# USB-COM.net
KiCad netlist of a schematic drawn in Altium Designer
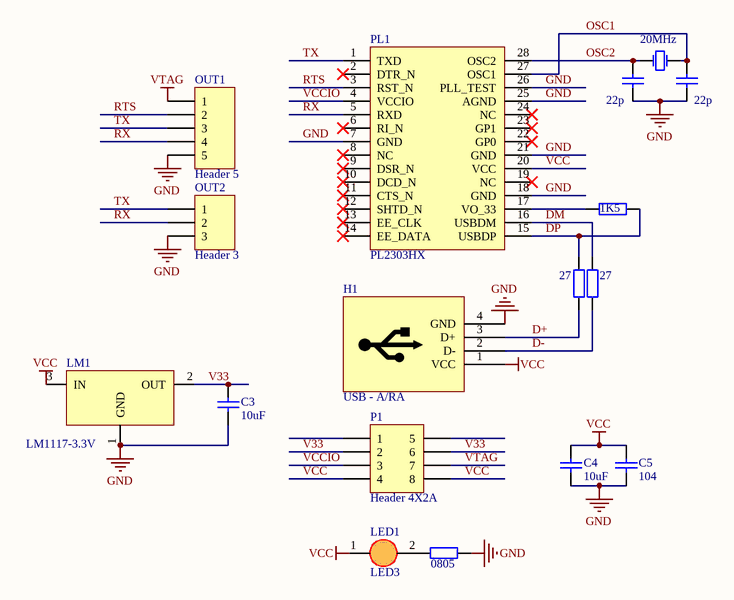
[diagram p0: USB-COM.SchDoc]

(export (version "E")
  (design (tool "Eeschema 10.0.6"))
  (components
    (comp (ref "C1")
      (value "22p")
      (footprint "C0805")
      (description "Capacitor")
      (fields (field (name "Comment") "Capacitor Ceramic") (field (name "PUBLISHER") "Altium Limited"))
      (libsource (lib "Schematic") (part "CapSMD"))
    )
    (comp (ref "C2")
      (value "22p")
      (footprint "C0805")
      (description "Capacitor")
      (fields (field (name "Comment") "Capacitor Ceramic") (field (name "PUBLISHER") "Altium Limited"))
      (libsource (lib "Schematic") (part "CapSMD"))
    )
    (comp (ref "C3") (value "10uF") (footprint "C1206") (libsource (lib "Schematic") (part "Cap SMD 1206")))
    (comp (ref "C4") (value "10uF") (footprint "C1206") (libsource (lib "Schematic") (part "Cap SMD 1206")))
    (comp (ref "C5")
      (value "104")
      (footprint "C0805")
      (description "Capacitor")
      (fields (field (name "Comment") "Capacitor Ceramic") (field (name "PUBLISHER") "Altium Limited"))
      (libsource (lib "Schematic") (part "CapSMD"))
    )
    (comp (ref "H1")
      (value "USB - A/RA")
      (footprint "USB-A-RA")
      (libsource (lib "Schematic") (part "USB - A/RA"))
    )
    (comp (ref "LED1")
      (value "LED3")
      (footprint "LED0805")
      (description "LED 3mm")
      (libsource (lib "Schematic") (part "LED 3mm"))
    )
    (comp (ref "LM1")
      (value "LM1117-3.3V")
      (footprint "LM1117-SOP")
      (description "800mA Low-Dropout Linear Regulator")
      (fields (field (name "CREATOR") "Nguyen Ba Bien"))
      (libsource (lib "General IC") (part "LM1117"))
    )
    (comp (ref "OUT1")
      (value "Header 5")
      (footprint "HDR1X5")
      (description "Header, 5-Pin")
      (fields (field (name "PUBLISHER") "Altium Limited"))
      (libsource (lib "Schematic") (part "Header 5"))
    )
    (comp (ref "OUT2")
      (value "Header 3")
      (footprint "HDR1X3")
      (description "Header, 3-Pin")
      (fields (field (name "PUBLISHER") "Altium Limited"))
      (libsource (lib "Schematic") (part "Header 3"))
    )
    (comp (ref "P1")
      (value "Header 4X2A")
      (footprint "HDR2X4_CEN")
      (description "Header, 4-Pin, Dual row")
      (fields (field (name "PUBLISHER") "Altium Limited"))
      (libsource (lib "Schematic") (part "Header 4X2A"))
    )
    (comp (ref "PL1")
      (value "PL2303HX")
      (footprint "PL2303-HX")
      (description "PL-2303 USB to RS-232 Bridge Controller")
      (fields (field (name "CREATOR") "Nguyen Ba Bien"))
      (libsource (lib "General IC") (part "PL2303HX"))
    )
    (comp (ref "R1")
      (value "1K5")
      (footprint "DIEN TRO 0805")
      (description "RES_08")
      (fields (field (name "PUBLISHER") "Altium Limited"))
      (libsource (lib "") (part "RES_08_1"))
    )
    (comp (ref "R2")
      (value "27")
      (footprint "DIEN TRO 0805")
      (description "RES_08")
      (fields (field (name "PUBLISHER") "Altium Limited"))
      (libsource (lib "Schematic") (part "RES_08"))
    )
    (comp (ref "R3")
      (value "27")
      (footprint "DIEN TRO 0805")
      (description "RES_08")
      (fields (field (name "PUBLISHER") "Altium Limited"))
      (libsource (lib "Schematic") (part "RES_08"))
    )
    (comp (ref "R4")
      (value "0805")
      (footprint "DIEN TRO 0805")
      (description "RES_08")
      (fields (field (name "PUBLISHER") "Altium Limited"))
      (libsource (lib "") (part "RES_08_1"))
    )
    (comp (ref "Y1")
      (value "20MHz")
      (footprint "XTAL")
      (description "Crystal Oscillator")
      (fields (field (name "PUBLISHER") "Altium Limited"))
      (libsource (lib "Schematic") (part "XTAL"))
    )
  )
  (nets
    (net (code "1") (name "/D+") (class "Default")
      (node (ref "H1") (pin "3") (pinfunction "D+_3") (pintype "passive"))
      (node (ref "R2") (pin "1") (pinfunction "1_1") (pintype "passive"))
    )
    (net (code "2") (name "/D-") (class "Default")
      (node (ref "H1") (pin "2") (pinfunction "D-_2") (pintype "passive"))
      (node (ref "R3") (pin "1") (pinfunction "1_1") (pintype "passive"))
    )
    (net (code "3") (name "/DM") (class "Default")
      (node (ref "PL1") (pin "16") (pinfunction "USBDM_16") (pintype "passive"))
      (node (ref "R3") (pin "2") (pinfunction "2_2") (pintype "passive"))
    )
    (net (code "4") (name "/DP") (class "Default")
      (node (ref "PL1") (pin "15") (pinfunction "USBDP_15") (pintype "passive"))
      (node (ref "R1") (pin "2") (pinfunction "2_2") (pintype "passive"))
      (node (ref "R2") (pin "2") (pinfunction "2_2") (pintype "passive"))
    )
    (net (code "5") (name "/OSC1") (class "Default")
      (node (ref "C2") (pin "2") (pinfunction "2_2") (pintype "passive"))
      (node (ref "PL1") (pin "27") (pinfunction "OSC1_27") (pintype "passive"))
      (node (ref "Y1") (pin "2") (pinfunction "OSC2_2") (pintype "passive"))
    )
    (net (code "6") (name "/OSC2") (class "Default")
      (node (ref "C1") (pin "2") (pinfunction "2_2") (pintype "passive"))
      (node (ref "PL1") (pin "28") (pinfunction "OSC2_28") (pintype "passive"))
      (node (ref "Y1") (pin "1") (pinfunction "OSC1_1") (pintype "passive"))
    )
    (net (code "7") (name "/RTS") (class "Default")
      (node (ref "OUT1") (pin "2") (pinfunction "2_2") (pintype "passive"))
      (node (ref "PL1") (pin "3") (pinfunction "RST_N_3") (pintype "passive"))
    )
    (net (code "8") (name "/RX") (class "Default")
      (node (ref "OUT1") (pin "4") (pinfunction "4_4") (pintype "passive"))
      (node (ref "OUT2") (pin "2") (pinfunction "2_2") (pintype "passive"))
      (node (ref "PL1") (pin "5") (pinfunction "RXD_5") (pintype "passive"))
    )
    (net (code "9") (name "/TX") (class "Default")
      (node (ref "OUT1") (pin "3") (pinfunction "3_3") (pintype "passive"))
      (node (ref "OUT2") (pin "1") (pinfunction "1_1") (pintype "passive"))
      (node (ref "PL1") (pin "1") (pinfunction "TXD_1") (pintype "passive"))
    )
    (net (code "10") (name "/V33") (class "Default")
      (node (ref "C3") (pin "2") (pinfunction "2_2") (pintype "passive"))
      (node (ref "LM1") (pin "2") (pinfunction "OUT_2") (pintype "passive"))
      (node (ref "P1") (pin "2") (pinfunction "2_2") (pintype "passive"))
      (node (ref "P1") (pin "6") (pinfunction "6_6") (pintype "passive"))
    )
    (net (code "11") (name "/VCCIO") (class "Default")
      (node (ref "P1") (pin "3") (pinfunction "3_3") (pintype "passive"))
      (node (ref "PL1") (pin "4") (pinfunction "VCCIO_4") (pintype "passive"))
    )
    (net (code "12") (name "GND") (class "Default")
      (node (ref "C1") (pin "1") (pinfunction "1_1") (pintype "passive"))
      (node (ref "C2") (pin "1") (pinfunction "1_1") (pintype "passive"))
      (node (ref "C3") (pin "1") (pinfunction "1_1") (pintype "passive"))
      (node (ref "C4") (pin "1") (pinfunction "1_1") (pintype "passive"))
      (node (ref "C5") (pin "1") (pinfunction "1_1") (pintype "passive"))
      (node (ref "H1") (pin "4") (pinfunction "GND_4") (pintype "passive"))
      (node (ref "LM1") (pin "1") (pinfunction "GND_1") (pintype "passive"))
      (node (ref "OUT1") (pin "5") (pinfunction "5_5") (pintype "passive"))
      (node (ref "OUT2") (pin "3") (pinfunction "3_3") (pintype "passive"))
      (node (ref "PL1") (pin "18") (pinfunction "GND_18") (pintype "passive"))
      (node (ref "PL1") (pin "21") (pinfunction "GND_21") (pintype "passive"))
      (node (ref "PL1") (pin "25") (pinfunction "AGND_25") (pintype "passive"))
      (node (ref "PL1") (pin "26") (pinfunction "PLL_TEST_26") (pintype "passive"))
      (node (ref "PL1") (pin "7") (pinfunction "GND_7") (pintype "passive"))
      (node (ref "R4") (pin "2") (pinfunction "2_2") (pintype "passive"))
    )
    (net (code "13") (name "Net-(LED1-K)") (class "Default")
      (node (ref "LED1") (pin "2") (pinfunction "K_2") (pintype "passive"))
      (node (ref "R4") (pin "1") (pinfunction "1_1") (pintype "passive"))
    )
    (net (code "14") (name "Net-(PL1-VO_33)") (class "Default")
      (node (ref "PL1") (pin "17") (pinfunction "VO_33_17") (pintype "passive"))
      (node (ref "R1") (pin "1") (pinfunction "1_1") (pintype "passive"))
    )
    (net (code "15") (name "VCC") (class "Default")
      (node (ref "C4") (pin "2") (pinfunction "2_2") (pintype "passive"))
      (node (ref "C5") (pin "2") (pinfunction "2_2") (pintype "passive"))
      (node (ref "H1") (pin "1") (pinfunction "VCC_1") (pintype "passive"))
      (node (ref "LED1") (pin "1") (pinfunction "A_1") (pintype "passive"))
      (node (ref "LM1") (pin "3") (pinfunction "IN_3") (pintype "passive"))
      (node (ref "P1") (pin "4") (pinfunction "4_4") (pintype "passive"))
      (node (ref "P1") (pin "8") (pinfunction "8_8") (pintype "passive"))
      (node (ref "PL1") (pin "20") (pinfunction "VCC_20") (pintype "passive"))
    )
    (net (code "16") (name "VTAG") (class "Default")
      (node (ref "OUT1") (pin "1") (pinfunction "1_1") (pintype "passive"))
      (node (ref "P1") (pin "7") (pinfunction "7_7") (pintype "passive"))
    )
    (net (code "17") (name "unconnected-(H1-Pad5)") (class "Default")
      (node (ref "H1") (pin "5") (pinfunction "5_5") (pintype "passive"))
    )
    (net (code "18") (name "unconnected-(H1-Pad6)") (class "Default")
      (node (ref "H1") (pin "6") (pinfunction "6_6") (pintype "passive"))
    )
    (net (code "19") (name "unconnected-(P1-Pad1)") (class "Default")
      (node (ref "P1") (pin "1") (pinfunction "1_1") (pintype "passive"))
    )
    (net (code "20") (name "unconnected-(P1-Pad5)") (class "Default")
      (node (ref "P1") (pin "5") (pinfunction "5_5") (pintype "passive"))
    )
    (net (code "21") (name "unconnected-(PL1-CTS_N-Pad11)") (class "Default")
      (node (ref "PL1") (pin "11") (pinfunction "CTS_N_11") (pintype "passive+no_connect"))
    )
    (net (code "22") (name "unconnected-(PL1-DCD_N-Pad10)") (class "Default")
      (node (ref "PL1") (pin "10") (pinfunction "DCD_N_10") (pintype "passive+no_connect"))
    )
    (net (code "23") (name "unconnected-(PL1-DSR_N-Pad9)") (class "Default")
      (node (ref "PL1") (pin "9") (pinfunction "DSR_N_9") (pintype "passive+no_connect"))
    )
    (net (code "24") (name "unconnected-(PL1-DTR_N-Pad2)") (class "Default")
      (node (ref "PL1") (pin "2") (pinfunction "DTR_N_2") (pintype "passive+no_connect"))
    )
    (net (code "25") (name "unconnected-(PL1-EE_CLK-Pad13)") (class "Default")
      (node (ref "PL1") (pin "13") (pinfunction "EE_CLK_13") (pintype "passive+no_connect"))
    )
    (net (code "26") (name "unconnected-(PL1-EE_DATA-Pad14)") (class "Default")
      (node (ref "PL1") (pin "14") (pinfunction "EE_DATA_14") (pintype "passive+no_connect"))
    )
    (net (code "27") (name "unconnected-(PL1-GP0-Pad22)") (class "Default")
      (node (ref "PL1") (pin "22") (pinfunction "GP0_22") (pintype "passive+no_connect"))
    )
    (net (code "28") (name "unconnected-(PL1-GP1-Pad23)") (class "Default")
      (node (ref "PL1") (pin "23") (pinfunction "GP1_23") (pintype "passive+no_connect"))
    )
    (net (code "29") (name "unconnected-(PL1-NC-Pad8)") (class "Default")
      (node (ref "PL1") (pin "8") (pinfunction "NC_8") (pintype "passive+no_connect"))
    )
    (net (code "30") (name "unconnected-(PL1-NC-Pad19)") (class "Default")
      (node (ref "PL1") (pin "19") (pinfunction "NC_19") (pintype "passive+no_connect"))
    )
    (net (code "31") (name "unconnected-(PL1-NC-Pad24)") (class "Default")
      (node (ref "PL1") (pin "24") (pinfunction "NC_24") (pintype "passive+no_connect"))
    )
    (net (code "32") (name "unconnected-(PL1-RI_N-Pad6)") (class "Default")
      (node (ref "PL1") (pin "6") (pinfunction "RI_N_6") (pintype "passive+no_connect"))
    )
    (net (code "33") (name "unconnected-(PL1-SHTD_N-Pad12)") (class "Default")
      (node (ref "PL1") (pin "12") (pinfunction "SHTD_N_12") (pintype "passive+no_connect"))
    )
  )
)
